# Adapter.net
KiCad netlist of a schematic drawn in EAGLE
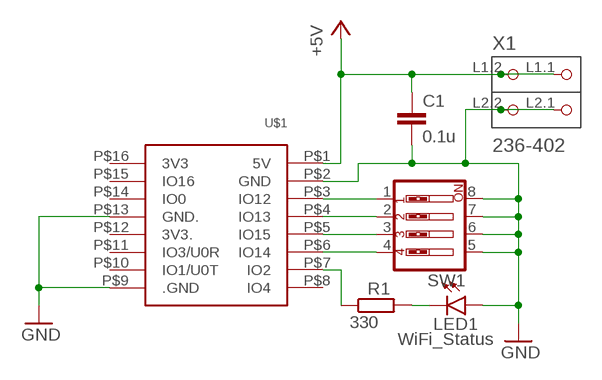
[diagram p0: schematic, sheet 1]

(export (version "E")
  (design (tool "Eeschema 10.0.6"))
  (components
    (comp (ref "C1")
      (value "0.1u")
      (footprint "eagle-import:C050-030X075")
      (libsource (lib "eagle-import") (part "C-EU050-030X075"))
    )
    (comp (ref "LED1")
      (value "WiFi_Status")
      (footprint "eagle-import:LED3MM")
      (fields (field (name "MF") "VISHAY SEMICONDUCTOR"))
      (libsource (lib "eagle-import") (part "TLLG4400"))
    )
    (comp (ref "R1")
      (value "330")
      (footprint "eagle-import:0204V")
      (libsource (lib "eagle-import") (part "R-EU_0204/2V"))
    )
    (comp (ref "SW1")
      (value "SW_DIP-4")
      (footprint "eagle-import:EDG-04")
      (libsource (lib "eagle-import") (part "SW_DIP-4"))
    )
    (comp (ref "U$1")
      (value "ESP32-CAM")
      (footprint "eagle-import:ESP32-CAM")
      (fields (field (name "MF") "AI-Thinker"))
      (libsource (lib "eagle-import") (part "ESP32-CAM"))
    )
    (comp (ref "X1")
      (value "236-402")
      (footprint "eagle-import:P-236-402")
      (libsource (lib "eagle-import") (part "236-402"))
    )
  )
  (nets
    (net (code "1") (name "+5V") (class "Default")
      (node (ref "C1") (pin "1") (pinfunction "1_1") (pintype "passive"))
      (node (ref "U$1") (pin "P$1") (pinfunction "5V_P$1") (pintype "bidirectional"))
      (node (ref "X1") (pin "L1.1") (pinfunction "P1.1_L1.1") (pintype "bidirectional"))
      (node (ref "X1") (pin "L1.2") (pinfunction "P1.2_L1.2") (pintype "bidirectional"))
    )
    (net (code "2") (name "GND") (class "Default")
      (node (ref "C1") (pin "2") (pinfunction "2_2") (pintype "passive"))
      (node (ref "LED1") (pin "A") (pinfunction "A_A") (pintype "passive"))
      (node (ref "SW1") (pin "5") (pinfunction "5_5") (pintype "passive"))
      (node (ref "SW1") (pin "6") (pinfunction "6_6") (pintype "passive"))
      (node (ref "SW1") (pin "7") (pinfunction "7_7") (pintype "passive"))
      (node (ref "SW1") (pin "8") (pinfunction "8_8") (pintype "passive"))
      (node (ref "U$1") (pin "P$13") (pinfunction "GND._P$13") (pintype "bidirectional"))
      (node (ref "U$1") (pin "P$2") (pinfunction "GND_P$2") (pintype "bidirectional"))
      (node (ref "U$1") (pin "P$9") (pinfunction ".GND_P$9") (pintype "bidirectional"))
      (node (ref "X1") (pin "L2.1") (pinfunction "P2.1_L2.1") (pintype "bidirectional"))
      (node (ref "X1") (pin "L2.2") (pinfunction "P2.2_L2.2") (pintype "bidirectional"))
    )
    (net (code "3") (name "Net-(LED1-C)") (class "Default")
      (node (ref "LED1") (pin "K") (pinfunction "C_K") (pintype "passive"))
      (node (ref "R1") (pin "2") (pinfunction "2_2") (pintype "passive"))
    )
    (net (code "4") (name "Net-(U$1-IO2)") (class "Default")
      (node (ref "R1") (pin "1") (pinfunction "1_1") (pintype "passive"))
      (node (ref "U$1") (pin "P$7") (pinfunction "IO2_P$7") (pintype "bidirectional"))
    )
    (net (code "5") (name "Net-(U$1-IO12)") (class "Default")
      (node (ref "SW1") (pin "1") (pinfunction "1_1") (pintype "passive"))
      (node (ref "U$1") (pin "P$3") (pinfunction "IO12_P$3") (pintype "bidirectional"))
    )
    (net (code "6") (name "Net-(U$1-IO13)") (class "Default")
      (node (ref "SW1") (pin "2") (pinfunction "2_2") (pintype "passive"))
      (node (ref "U$1") (pin "P$4") (pinfunction "IO13_P$4") (pintype "bidirectional"))
    )
    (net (code "7") (name "Net-(U$1-IO14)") (class "Default")
      (node (ref "SW1") (pin "4") (pinfunction "4_4") (pintype "passive"))
      (node (ref "U$1") (pin "P$6") (pinfunction "IO14_P$6") (pintype "bidirectional"))
    )
    (net (code "8") (name "Net-(U$1-IO15)") (class "Default")
      (node (ref "SW1") (pin "3") (pinfunction "3_3") (pintype "passive"))
      (node (ref "U$1") (pin "P$5") (pinfunction "IO15_P$5") (pintype "bidirectional"))
    )
    (net (code "9") (name "unconnected-(U$1-3V3-PadP$16)") (class "Default")
      (node (ref "U$1") (pin "P$16") (pinfunction "3V3_P$16") (pintype "bidirectional"))
    )
    (net (code "10") (name "unconnected-(U$1-3V3.-PadP$12)") (class "Default")
      (node (ref "U$1") (pin "P$12") (pinfunction "3V3._P$12") (pintype "bidirectional"))
    )
    (net (code "11") (name "unconnected-(U$1-IO0-PadP$14)") (class "Default")
      (node (ref "U$1") (pin "P$14") (pinfunction "IO0_P$14") (pintype "bidirectional"))
    )
    (net (code "12") (name "unconnected-(U$1-IO1{slash}U0T-PadP$10)") (class "Default")
      (node (ref "U$1") (pin "P$10") (pinfunction "IO1/U0T_P$10") (pintype "bidirectional"))
    )
    (net (code "13") (name "unconnected-(U$1-IO3{slash}U0R-PadP$11)") (class "Default")
      (node (ref "U$1") (pin "P$11") (pinfunction "IO3/U0R_P$11") (pintype "bidirectional"))
    )
    (net (code "14") (name "unconnected-(U$1-IO4-PadP$8)") (class "Default")
      (node (ref "U$1") (pin "P$8") (pinfunction "IO4_P$8") (pintype "bidirectional"))
    )
    (net (code "15") (name "unconnected-(U$1-IO16-PadP$15)") (class "Default")
      (node (ref "U$1") (pin "P$15") (pinfunction "IO16_P$15") (pintype "bidirectional"))
    )
  )
)
